# remote_glove_bluetooth_2021-02-27.net
KiCad netlist of a schematic drawn in EasyEDA
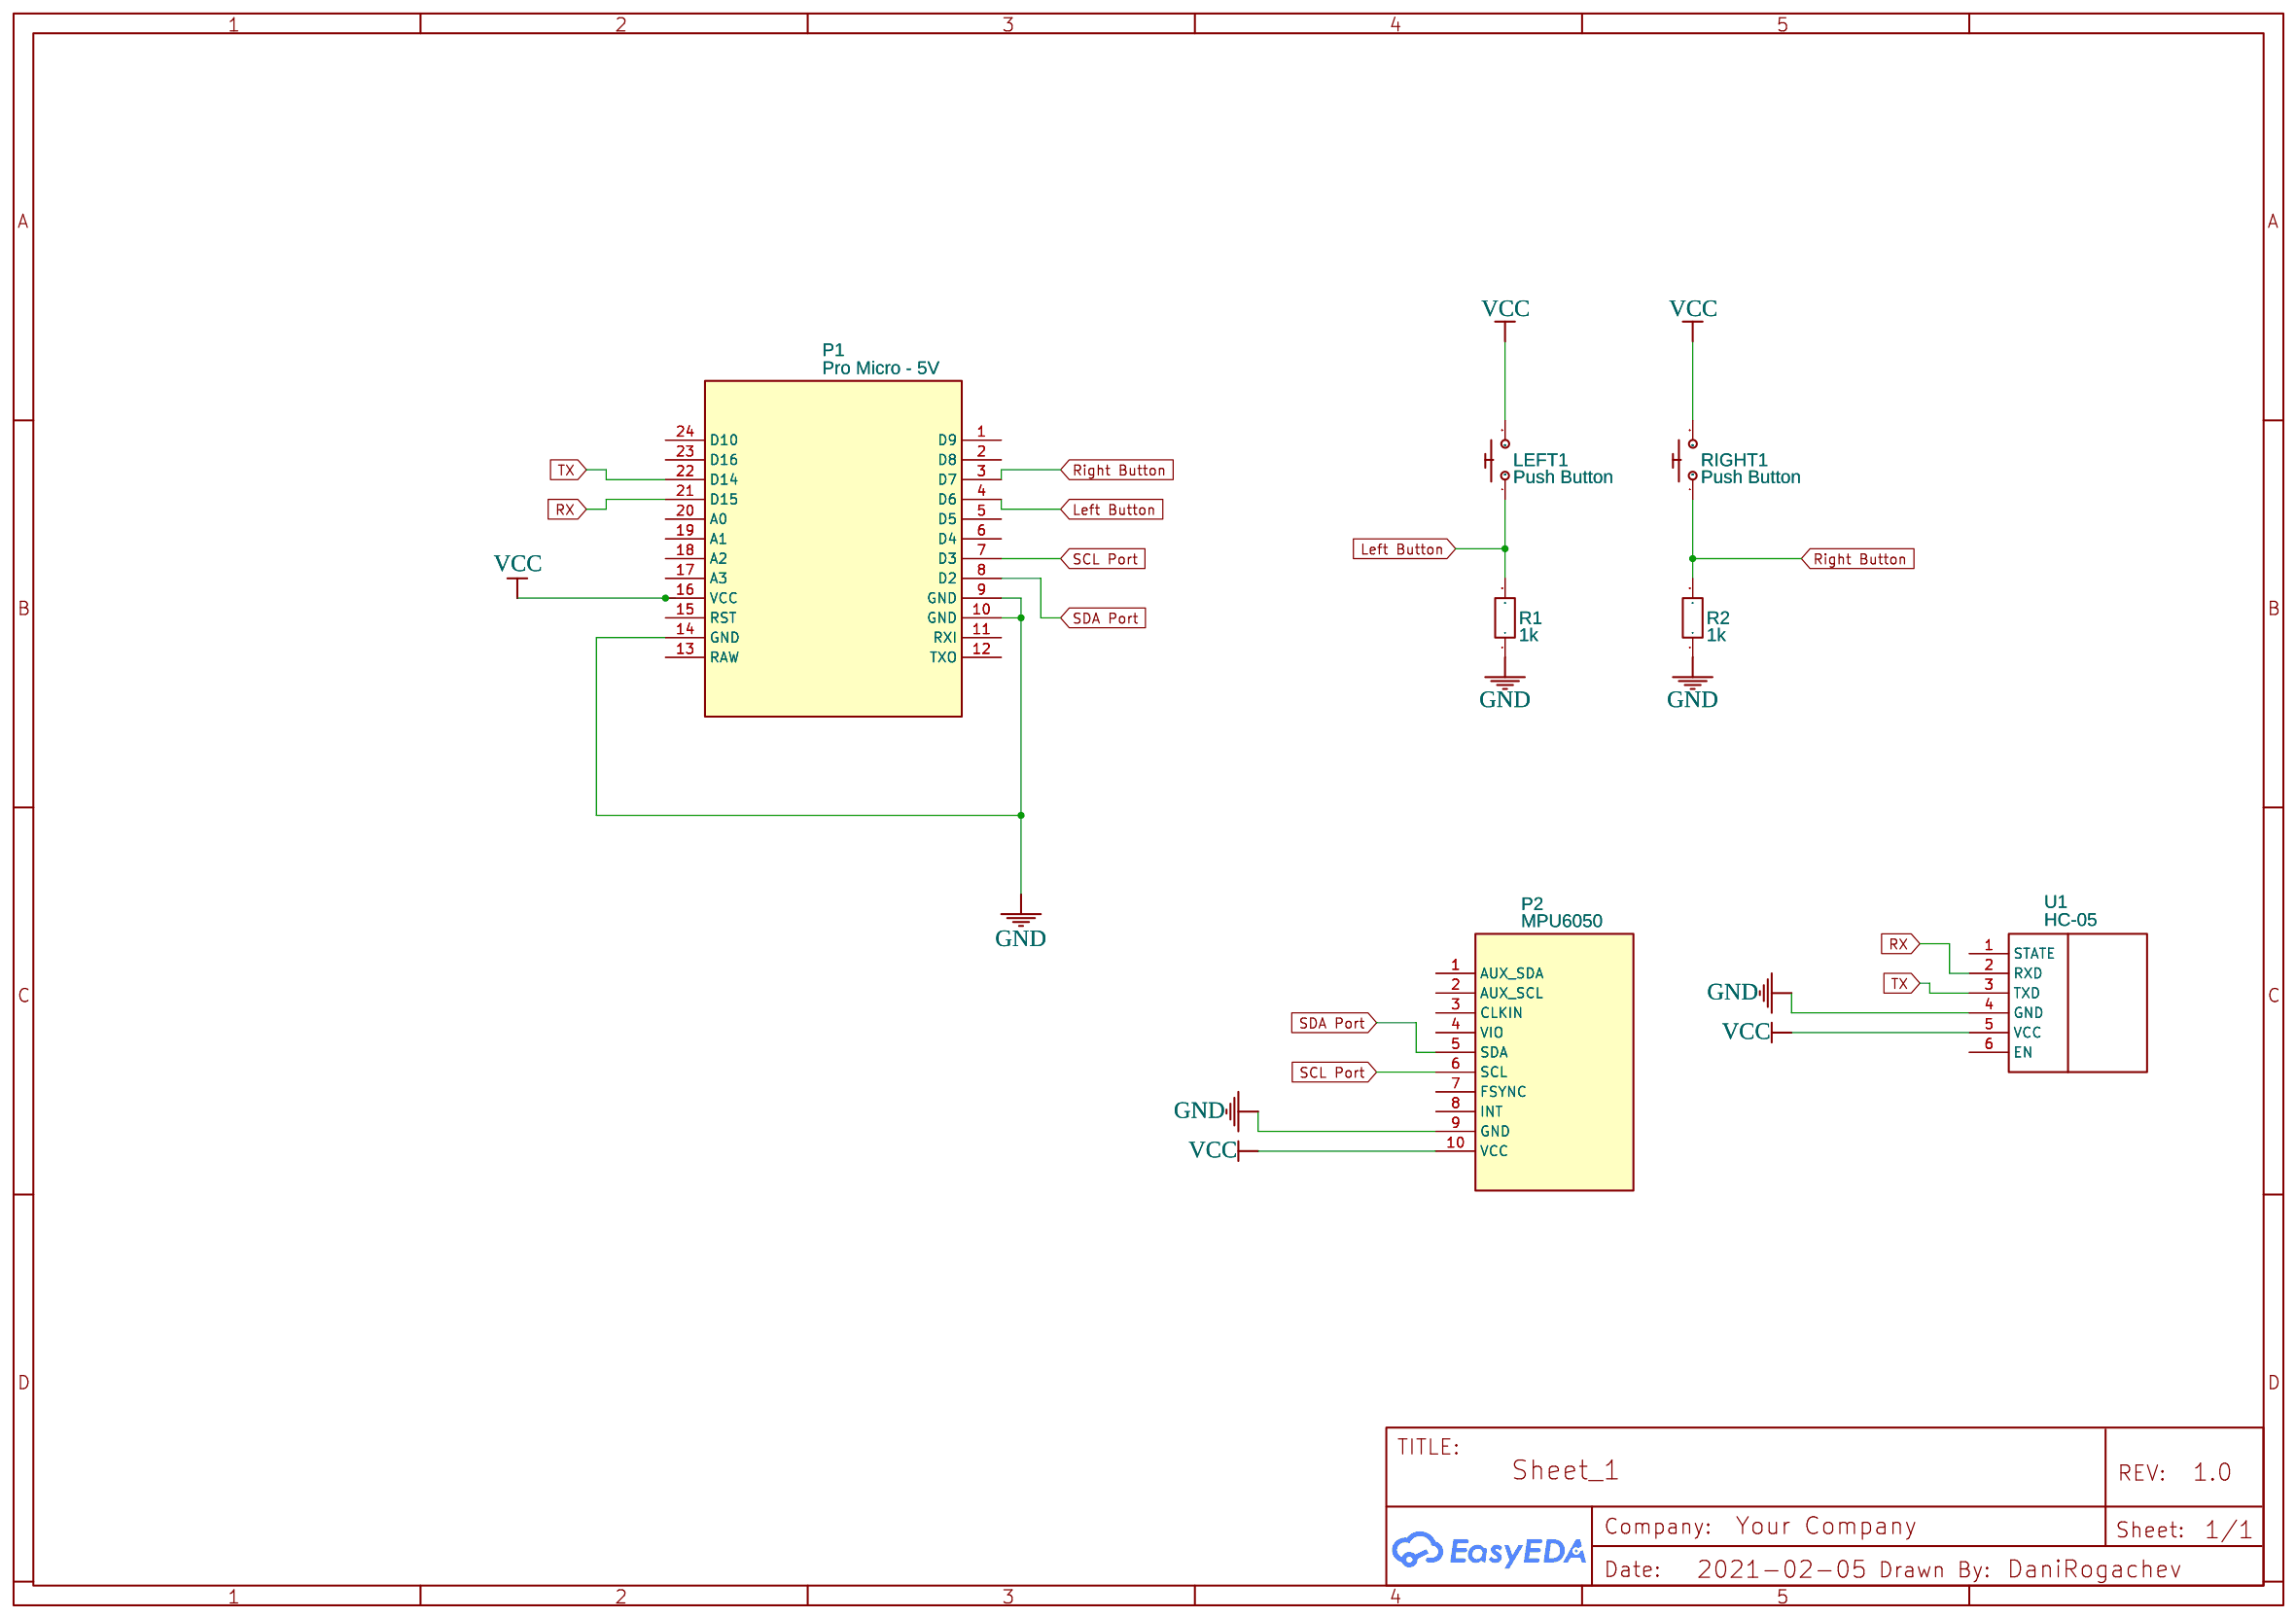
[diagram p0: Transceiver_scheme_hc05]
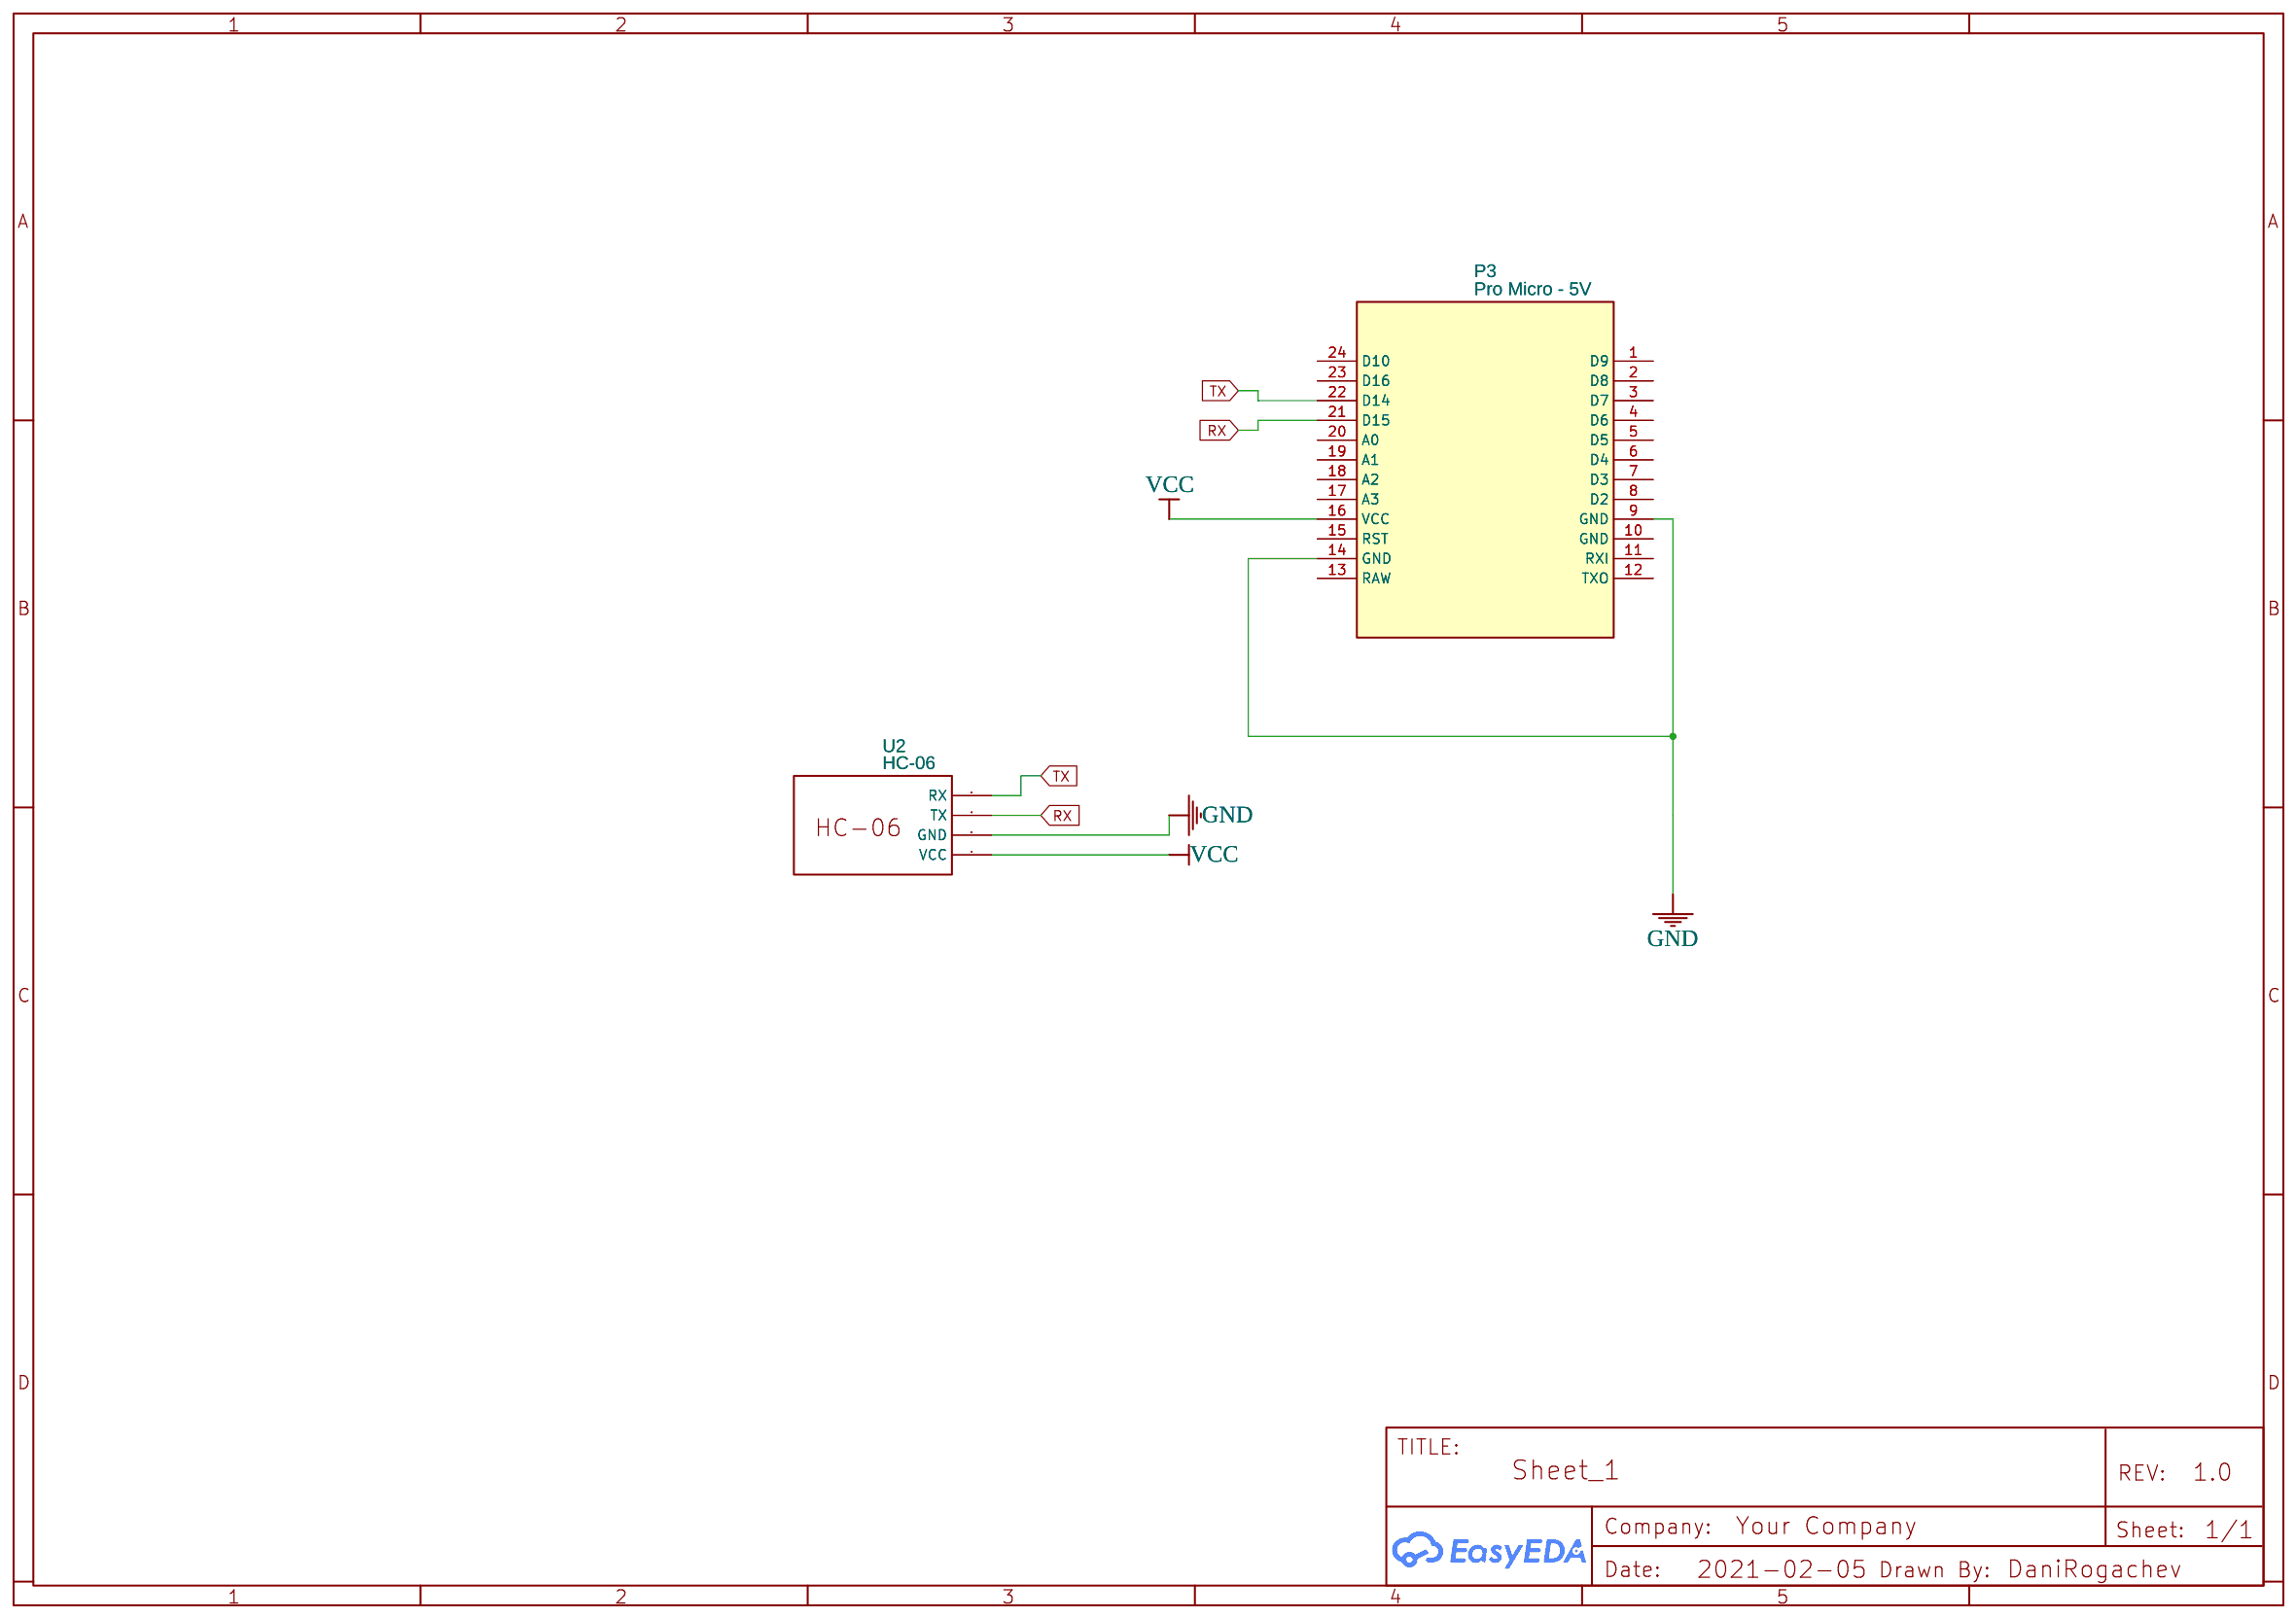
[diagram p1: Receiver_scheme_hc06]

(export (version "E")
  (design (tool "Eeschema 10.0.6"))
  (components
    (comp (ref "LEFT1")
      (value "Push Button")
      (fields (field (name "BOM_Supplier Part") "COM-08720"))
      (libsource (lib "") (part "Push Button"))
    )
    (comp (ref "P1") (value "Pro Micro - 5V") (libsource (lib "") (part "Pro Micro - 5V")))
    (comp (ref "P2") (value "MPU6050") (libsource (lib "") (part "MPU6050")))
    (comp (ref "R1") (value "1k") (libsource (lib "") (part "R_0603_EU")))
    (comp (ref "R2") (value "1k") (libsource (lib "") (part "R_0603_EU")))
    (comp (ref "RIGHT1")
      (value "Push Button")
      (fields (field (name "BOM_Supplier Part") "COM-08720"))
      (libsource (lib "") (part "Push Button_1"))
    )
    (comp (ref "U1") (value "HC-05") (libsource (lib "") (part "HC-05")))
    (comp (ref "P3") (value "Pro Micro - 5V") (libsource (lib "") (part "Pro Micro - 5V")))
    (comp (ref "U2") (value "HC-06") (libsource (lib "") (part "HC-06")))
  )
  (nets
    (net (code "1") (name "GND") (class "Default")
      (node (ref "P1") (pin "10") (pinfunction "GND_10") (pintype "unspecified"))
      (node (ref "P1") (pin "14") (pinfunction "GND_14") (pintype "unspecified"))
      (node (ref "P1") (pin "9") (pinfunction "GND_9") (pintype "unspecified"))
      (node (ref "P2") (pin "9") (pinfunction "GND_9") (pintype "unspecified"))
      (node (ref "P3") (pin "14") (pinfunction "GND_14") (pintype "unspecified"))
      (node (ref "P3") (pin "9") (pinfunction "GND_9") (pintype "unspecified"))
      (node (ref "R1") (pin "1") (pinfunction "1_1") (pintype "unspecified"))
      (node (ref "R2") (pin "1") (pinfunction "1_1") (pintype "unspecified"))
      (node (ref "U1") (pin "4") (pinfunction "GND_4") (pintype "unspecified"))
      (node (ref "U2") (pin "3") (pinfunction "GND_3") (pintype "unspecified"))
    )
    (net (code "2") (name "Left Button") (class "Default")
      (node (ref "LEFT1") (pin "1") (pinfunction "P$1_1") (pintype "unspecified"))
      (node (ref "P1") (pin "4") (pinfunction "D6_4") (pintype "unspecified"))
      (node (ref "R1") (pin "2") (pinfunction "2_2") (pintype "unspecified"))
    )
    (net (code "3") (name "RX") (class "Default")
      (node (ref "P1") (pin "21") (pinfunction "D15_21") (pintype "unspecified"))
      (node (ref "P3") (pin "21") (pinfunction "D15_21") (pintype "unspecified"))
      (node (ref "U1") (pin "2") (pinfunction "RXD_2") (pintype "unspecified"))
      (node (ref "U2") (pin "2") (pinfunction "TX_2") (pintype "unspecified"))
    )
    (net (code "4") (name "Right Button") (class "Default")
      (node (ref "P1") (pin "3") (pinfunction "D7_3") (pintype "unspecified"))
      (node (ref "R2") (pin "2") (pinfunction "2_2") (pintype "unspecified"))
      (node (ref "RIGHT1") (pin "1") (pinfunction "P$1_1") (pintype "unspecified"))
    )
    (net (code "5") (name "SCL Port") (class "Default")
      (node (ref "P1") (pin "7") (pinfunction "D3_7") (pintype "unspecified"))
      (node (ref "P2") (pin "6") (pinfunction "SCL_6") (pintype "unspecified"))
    )
    (net (code "6") (name "SDA Port") (class "Default")
      (node (ref "P1") (pin "8") (pinfunction "D2_8") (pintype "unspecified"))
      (node (ref "P2") (pin "5") (pinfunction "SDA_5") (pintype "unspecified"))
    )
    (net (code "7") (name "TX") (class "Default")
      (node (ref "P1") (pin "22") (pinfunction "D14_22") (pintype "unspecified"))
      (node (ref "P3") (pin "22") (pinfunction "D14_22") (pintype "unspecified"))
      (node (ref "U1") (pin "3") (pinfunction "TXD_3") (pintype "unspecified"))
      (node (ref "U2") (pin "1") (pinfunction "RX_1") (pintype "unspecified"))
    )
    (net (code "8") (name "VCC") (class "Default")
      (node (ref "LEFT1") (pin "2") (pinfunction "P$2_2") (pintype "unspecified"))
      (node (ref "P1") (pin "16") (pinfunction "VCC_16") (pintype "unspecified"))
      (node (ref "P2") (pin "10") (pinfunction "VCC_10") (pintype "unspecified"))
      (node (ref "P3") (pin "16") (pinfunction "VCC_16") (pintype "unspecified"))
      (node (ref "RIGHT1") (pin "2") (pinfunction "P$2_2") (pintype "unspecified"))
      (node (ref "U1") (pin "5") (pinfunction "VCC_5") (pintype "unspecified"))
      (node (ref "U2") (pin "4") (pinfunction "VCC_4") (pintype "unspecified"))
    )
    (net (code "9") (name "unconnected-(P1-A0-Pad20)") (class "Default")
      (node (ref "P1") (pin "20") (pinfunction "A0_20") (pintype "unspecified"))
    )
    (net (code "10") (name "unconnected-(P1-A1-Pad19)") (class "Default")
      (node (ref "P1") (pin "19") (pinfunction "A1_19") (pintype "unspecified"))
    )
    (net (code "11") (name "unconnected-(P1-A2-Pad18)") (class "Default")
      (node (ref "P1") (pin "18") (pinfunction "A2_18") (pintype "unspecified"))
    )
    (net (code "12") (name "unconnected-(P1-A3-Pad17)") (class "Default")
      (node (ref "P1") (pin "17") (pinfunction "A3_17") (pintype "unspecified"))
    )
    (net (code "13") (name "unconnected-(P1-D4-Pad6)") (class "Default")
      (node (ref "P1") (pin "6") (pinfunction "D4_6") (pintype "unspecified"))
    )
    (net (code "14") (name "unconnected-(P1-D5-Pad5)") (class "Default")
      (node (ref "P1") (pin "5") (pinfunction "D5_5") (pintype "unspecified"))
    )
    (net (code "15") (name "unconnected-(P1-D8-Pad2)") (class "Default")
      (node (ref "P1") (pin "2") (pinfunction "D8_2") (pintype "unspecified"))
    )
    (net (code "16") (name "unconnected-(P1-D9-Pad1)") (class "Default")
      (node (ref "P1") (pin "1") (pinfunction "D9_1") (pintype "unspecified"))
    )
    (net (code "17") (name "unconnected-(P1-D10-Pad24)") (class "Default")
      (node (ref "P1") (pin "24") (pinfunction "D10_24") (pintype "unspecified"))
    )
    (net (code "18") (name "unconnected-(P1-D16-Pad23)") (class "Default")
      (node (ref "P1") (pin "23") (pinfunction "D16_23") (pintype "unspecified"))
    )
    (net (code "19") (name "unconnected-(P1-RAW-Pad13)") (class "Default")
      (node (ref "P1") (pin "13") (pinfunction "RAW_13") (pintype "unspecified"))
    )
    (net (code "20") (name "unconnected-(P1-RST-Pad15)") (class "Default")
      (node (ref "P1") (pin "15") (pinfunction "RST_15") (pintype "unspecified"))
    )
    (net (code "21") (name "unconnected-(P1-RXI-Pad11)") (class "Default")
      (node (ref "P1") (pin "11") (pinfunction "RXI_11") (pintype "unspecified"))
    )
    (net (code "22") (name "unconnected-(P1-TXO-Pad12)") (class "Default")
      (node (ref "P1") (pin "12") (pinfunction "TXO_12") (pintype "unspecified"))
    )
    (net (code "23") (name "unconnected-(P2-AUX_SCL-Pad2)") (class "Default")
      (node (ref "P2") (pin "2") (pinfunction "AUX_SCL_2") (pintype "unspecified"))
    )
    (net (code "24") (name "unconnected-(P2-AUX_SDA-Pad1)") (class "Default")
      (node (ref "P2") (pin "1") (pinfunction "AUX_SDA_1") (pintype "unspecified"))
    )
    (net (code "25") (name "unconnected-(P2-CLKIN-Pad3)") (class "Default")
      (node (ref "P2") (pin "3") (pinfunction "CLKIN_3") (pintype "unspecified"))
    )
    (net (code "26") (name "unconnected-(P2-FSYNC-Pad7)") (class "Default")
      (node (ref "P2") (pin "7") (pinfunction "FSYNC_7") (pintype "unspecified"))
    )
    (net (code "27") (name "unconnected-(P2-INT-Pad8)") (class "Default")
      (node (ref "P2") (pin "8") (pinfunction "INT_8") (pintype "unspecified"))
    )
    (net (code "28") (name "unconnected-(P2-VIO-Pad4)") (class "Default")
      (node (ref "P2") (pin "4") (pinfunction "VIO_4") (pintype "unspecified"))
    )
    (net (code "29") (name "unconnected-(P3-A0-Pad20)") (class "Default")
      (node (ref "P3") (pin "20") (pinfunction "A0_20") (pintype "unspecified"))
    )
    (net (code "30") (name "unconnected-(P3-A1-Pad19)") (class "Default")
      (node (ref "P3") (pin "19") (pinfunction "A1_19") (pintype "unspecified"))
    )
    (net (code "31") (name "unconnected-(P3-A2-Pad18)") (class "Default")
      (node (ref "P3") (pin "18") (pinfunction "A2_18") (pintype "unspecified"))
    )
    (net (code "32") (name "unconnected-(P3-A3-Pad17)") (class "Default")
      (node (ref "P3") (pin "17") (pinfunction "A3_17") (pintype "unspecified"))
    )
    (net (code "33") (name "unconnected-(P3-D2-Pad8)") (class "Default")
      (node (ref "P3") (pin "8") (pinfunction "D2_8") (pintype "unspecified"))
    )
    (net (code "34") (name "unconnected-(P3-D3-Pad7)") (class "Default")
      (node (ref "P3") (pin "7") (pinfunction "D3_7") (pintype "unspecified"))
    )
    (net (code "35") (name "unconnected-(P3-D4-Pad6)") (class "Default")
      (node (ref "P3") (pin "6") (pinfunction "D4_6") (pintype "unspecified"))
    )
    (net (code "36") (name "unconnected-(P3-D5-Pad5)") (class "Default")
      (node (ref "P3") (pin "5") (pinfunction "D5_5") (pintype "unspecified"))
    )
    (net (code "37") (name "unconnected-(P3-D6-Pad4)") (class "Default")
      (node (ref "P3") (pin "4") (pinfunction "D6_4") (pintype "unspecified"))
    )
    (net (code "38") (name "unconnected-(P3-D7-Pad3)") (class "Default")
      (node (ref "P3") (pin "3") (pinfunction "D7_3") (pintype "unspecified"))
    )
    (net (code "39") (name "unconnected-(P3-D8-Pad2)") (class "Default")
      (node (ref "P3") (pin "2") (pinfunction "D8_2") (pintype "unspecified"))
    )
    (net (code "40") (name "unconnected-(P3-D9-Pad1)") (class "Default")
      (node (ref "P3") (pin "1") (pinfunction "D9_1") (pintype "unspecified"))
    )
    (net (code "41") (name "unconnected-(P3-D10-Pad24)") (class "Default")
      (node (ref "P3") (pin "24") (pinfunction "D10_24") (pintype "unspecified"))
    )
    (net (code "42") (name "unconnected-(P3-D16-Pad23)") (class "Default")
      (node (ref "P3") (pin "23") (pinfunction "D16_23") (pintype "unspecified"))
    )
    (net (code "43") (name "unconnected-(P3-GND-Pad10)") (class "Default")
      (node (ref "P3") (pin "10") (pinfunction "GND_10") (pintype "unspecified"))
    )
    (net (code "44") (name "unconnected-(P3-RAW-Pad13)") (class "Default")
      (node (ref "P3") (pin "13") (pinfunction "RAW_13") (pintype "unspecified"))
    )
    (net (code "45") (name "unconnected-(P3-RST-Pad15)") (class "Default")
      (node (ref "P3") (pin "15") (pinfunction "RST_15") (pintype "unspecified"))
    )
    (net (code "46") (name "unconnected-(P3-RXI-Pad11)") (class "Default")
      (node (ref "P3") (pin "11") (pinfunction "RXI_11") (pintype "unspecified"))
    )
    (net (code "47") (name "unconnected-(P3-TXO-Pad12)") (class "Default")
      (node (ref "P3") (pin "12") (pinfunction "TXO_12") (pintype "unspecified"))
    )
    (net (code "48") (name "unconnected-(U1-EN-Pad6)") (class "Default")
      (node (ref "U1") (pin "6") (pinfunction "EN_6") (pintype "unspecified"))
    )
    (net (code "49") (name "unconnected-(U1-STATE-Pad1)") (class "Default")
      (node (ref "U1") (pin "1") (pinfunction "STATE_1") (pintype "unspecified"))
    )
  )
)
